# POWER_SUPPLY_1.net
KiCad netlist of a schematic drawn in EAGLE
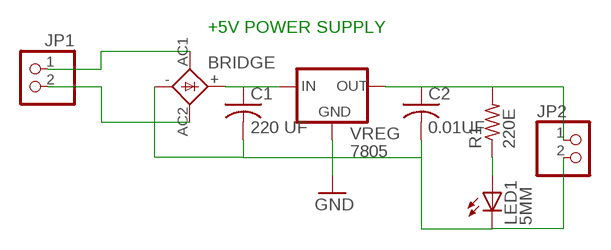
[diagram p0: schematic, sheet 1]

(export (version "E")
  (design (tool "Eeschema 10.0.6"))
  (components
    (comp (ref "BRIDGE")
      (value "GBPC1")
      (footprint "eagle-import:GBPC1")
      (libsource (lib "eagle-import") (part "GBPC1"))
    )
    (comp (ref "C1")
      (value "220 UF")
      (footprint "eagle-import:C050-030X075")
      (libsource (lib "eagle-import") (part "C-US050-030X075"))
    )
    (comp (ref "C2")
      (value "0.01UF")
      (footprint "eagle-import:C050-030X075")
      (libsource (lib "eagle-import") (part "C-US050-030X075"))
    )
    (comp (ref "JP1")
      (value "PINHD-1X2/90")
      (footprint "eagle-import:1X02_90")
      (libsource (lib "eagle-import") (part "PINHD-1X2/90"))
    )
    (comp (ref "JP2")
      (value "PINHD-1X2/90")
      (footprint "eagle-import:1X02_90")
      (libsource (lib "eagle-import") (part "PINHD-1X2/90"))
    )
    (comp (ref "LED1")
      (value "5MM")
      (footprint "eagle-import:LED5MM")
      (libsource (lib "eagle-import") (part "LED5MM"))
    )
    (comp (ref "R1")
      (value "220E")
      (footprint "eagle-import:0204_7")
      (libsource (lib "eagle-import") (part "R-US_0204/7"))
    )
    (comp (ref "VREG")
      (value "7805")
      (footprint "eagle-import:78XXL")
      (libsource (lib "eagle-import") (part "78XXL"))
    )
  )
  (nets
    (net (code "1") (name "GND") (class "Default")
      (node (ref "BRIDGE") (pin "-") (pinfunction "-_-") (pintype "passive"))
      (node (ref "C1") (pin "2") (pinfunction "2_2") (pintype "passive"))
      (node (ref "C2") (pin "2") (pinfunction "2_2") (pintype "passive"))
      (node (ref "JP2") (pin "2") (pinfunction "2_2") (pintype "passive"))
      (node (ref "LED1") (pin "K") (pinfunction "C_K") (pintype "passive"))
      (node (ref "VREG") (pin "GND") (pinfunction "GND_GND") (pintype "input"))
    )
    (net (code "2") (name "Net-(BRIDGE-Pad+)") (class "Default")
      (node (ref "BRIDGE") (pin "+") (pinfunction "+_+") (pintype "passive"))
      (node (ref "C1") (pin "1") (pinfunction "1_1") (pintype "passive"))
      (node (ref "VREG") (pin "IN") (pinfunction "IN_IN") (pintype "input"))
    )
    (net (code "3") (name "Net-(BRIDGE-PadAC1)") (class "Default")
      (node (ref "BRIDGE") (pin "AC1") (pinfunction "AC1_AC1") (pintype "passive"))
      (node (ref "JP1") (pin "1") (pinfunction "1_1") (pintype "passive"))
    )
    (net (code "4") (name "Net-(BRIDGE-PadAC2)") (class "Default")
      (node (ref "BRIDGE") (pin "AC2") (pinfunction "AC2_AC2") (pintype "passive"))
      (node (ref "JP1") (pin "2") (pinfunction "2_2") (pintype "passive"))
    )
    (net (code "5") (name "Net-(C2-Pad1)") (class "Default")
      (node (ref "C2") (pin "1") (pinfunction "1_1") (pintype "passive"))
      (node (ref "JP2") (pin "1") (pinfunction "1_1") (pintype "passive"))
      (node (ref "R1") (pin "2") (pinfunction "2_2") (pintype "passive"))
      (node (ref "VREG") (pin "OUT") (pinfunction "OUT_OUT") (pintype "passive"))
    )
    (net (code "6") (name "Net-(LED1-PadA)") (class "Default")
      (node (ref "LED1") (pin "A") (pinfunction "A_A") (pintype "passive"))
      (node (ref "R1") (pin "1") (pinfunction "1_1") (pintype "passive"))
    )
  )
)
